# LcsNodes-Diagnostic-Board-B_02_10.net
KiCad netlist of a schematic drawn in EasyEDA
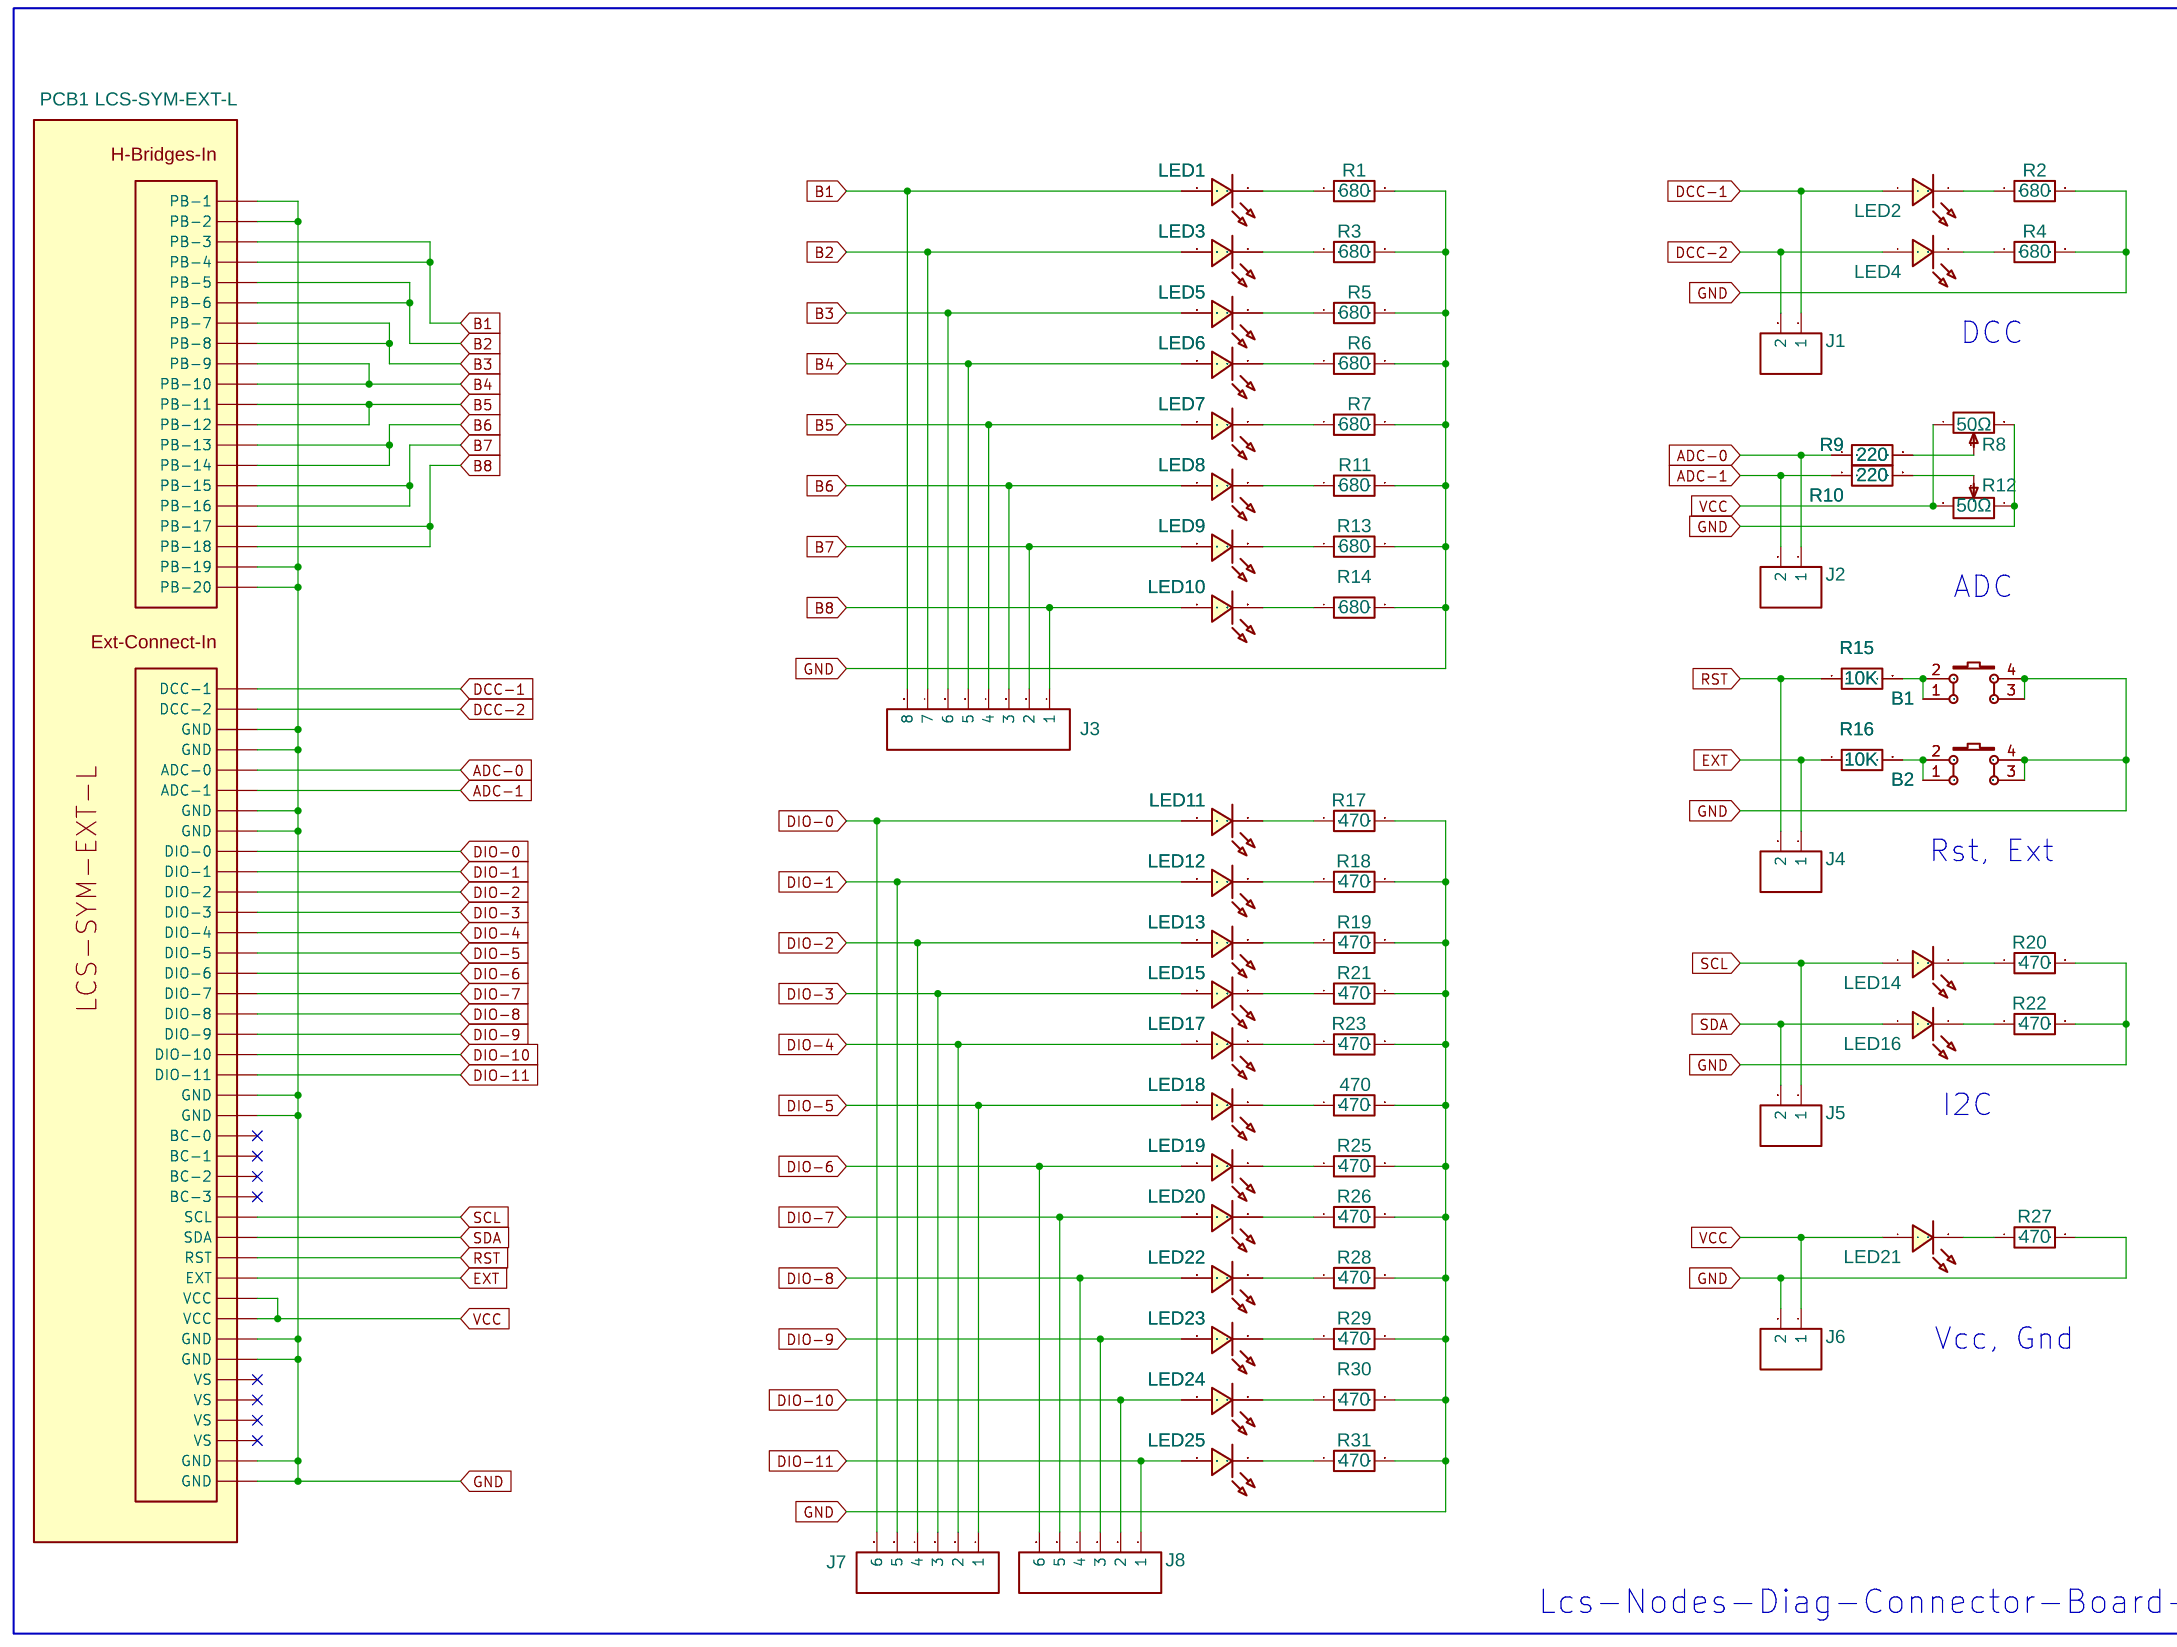
[diagram p0: schematic sheet]

(export (version "E")
  (design (tool "Eeschema 10.0.6"))
  (components
    (comp (ref "470") (value "470") (libsource (lib "") (part "R_0805_EU_1")))
    (comp (ref "B1")
      (value "Opt")
      (fields (field (name "Manufacturer Part") "K2-1102DP-E4SW-04") (field (name "Manufacturer") "韩国韩荣"))
      (libsource (lib "") (part "K4-6×6_TH"))
    )
    (comp (ref "B2")
      (value "Opt")
      (fields (field (name "Manufacturer Part") "K2-1102DP-E4SW-04") (field (name "Manufacturer") "韩国韩荣"))
      (libsource (lib "") (part "K4-6×6_TH"))
    )
    (comp (ref "J1") (value "HDR-M-2.54_1x2") (libsource (lib "") (part "HDR-M-2.54_1x2")))
    (comp (ref "J2") (value "HDR-M-2.54_1x2") (libsource (lib "") (part "HDR-M-2.54_1x2")))
    (comp (ref "J3") (value "HDR-M-2.54_1x8") (libsource (lib "") (part "HDR-M-2.54_1x8")))
    (comp (ref "J4") (value "HDR-M-2.54_1x2") (libsource (lib "") (part "HDR-M-2.54_1x2")))
    (comp (ref "J5") (value "HDR-M-2.54_1x2") (libsource (lib "") (part "HDR-M-2.54_1x2")))
    (comp (ref "J6") (value "HDR-M-2.54_1x2") (libsource (lib "") (part "HDR-M-2.54_1x2")))
    (comp (ref "J7") (value "HDR-M-2.54_1x6") (libsource (lib "") (part "HDR-M-2.54_1x6")))
    (comp (ref "J8") (value "HDR-M-2.54_1x6") (libsource (lib "") (part "HDR-M-2.54_1x6")))
    (comp (ref "LED1")
      (value "LED-0805_G")
      (fields (field (name "Manufacturer Part") "NCD0805G1") (field (name "Manufacturer") "国星光电"))
      (libsource (lib "") (part "LED-0805_G"))
    )
    (comp (ref "LED2")
      (value "LED-0805_G")
      (fields (field (name "Manufacturer Part") "NCD0805G1") (field (name "Manufacturer") "国星光电"))
      (libsource (lib "") (part "LED-0805_G"))
    )
    (comp (ref "LED3")
      (value "LED-0805_G")
      (fields (field (name "Manufacturer Part") "NCD0805G1") (field (name "Manufacturer") "国星光电"))
      (libsource (lib "") (part "LED-0805_G"))
    )
    (comp (ref "LED4")
      (value "LED-0805_G")
      (fields (field (name "Manufacturer Part") "NCD0805G1") (field (name "Manufacturer") "国星光电"))
      (libsource (lib "") (part "LED-0805_G"))
    )
    (comp (ref "LED5")
      (value "LED-0805_G")
      (fields (field (name "Manufacturer Part") "NCD0805G1") (field (name "Manufacturer") "国星光电"))
      (libsource (lib "") (part "LED-0805_G"))
    )
    (comp (ref "LED6")
      (value "LED-0805_G")
      (fields (field (name "Manufacturer Part") "NCD0805G1") (field (name "Manufacturer") "国星光电"))
      (libsource (lib "") (part "LED-0805_G"))
    )
    (comp (ref "LED7")
      (value "LED-0805_G")
      (fields (field (name "Manufacturer Part") "NCD0805G1") (field (name "Manufacturer") "国星光电"))
      (libsource (lib "") (part "LED-0805_G"))
    )
    (comp (ref "LED8")
      (value "LED-0805_G")
      (fields (field (name "Manufacturer Part") "NCD0805G1") (field (name "Manufacturer") "国星光电"))
      (libsource (lib "") (part "LED-0805_G"))
    )
    (comp (ref "LED9")
      (value "LED-0805_G")
      (fields (field (name "Manufacturer Part") "NCD0805G1") (field (name "Manufacturer") "国星光电"))
      (libsource (lib "") (part "LED-0805_G"))
    )
    (comp (ref "LED10")
      (value "LED-0805_G")
      (fields (field (name "Manufacturer Part") "NCD0805G1") (field (name "Manufacturer") "国星光电"))
      (libsource (lib "") (part "LED-0805_G"))
    )
    (comp (ref "LED11")
      (value "LED-0805_G")
      (fields (field (name "Manufacturer Part") "NCD0805G1") (field (name "Manufacturer") "国星光电"))
      (libsource (lib "") (part "LED-0805_G"))
    )
    (comp (ref "LED12")
      (value "LED-0805_G")
      (fields (field (name "Manufacturer Part") "NCD0805G1") (field (name "Manufacturer") "国星光电"))
      (libsource (lib "") (part "LED-0805_G"))
    )
    (comp (ref "LED13")
      (value "LED-0805_G")
      (fields (field (name "Manufacturer Part") "NCD0805G1") (field (name "Manufacturer") "国星光电"))
      (libsource (lib "") (part "LED-0805_G"))
    )
    (comp (ref "LED14")
      (value "LED-0805_G")
      (fields (field (name "Manufacturer Part") "NCD0805G1") (field (name "Manufacturer") "国星光电"))
      (libsource (lib "") (part "LED-0805_G"))
    )
    (comp (ref "LED15")
      (value "LED-0805_G")
      (fields (field (name "Manufacturer Part") "NCD0805G1") (field (name "Manufacturer") "国星光电"))
      (libsource (lib "") (part "LED-0805_G"))
    )
    (comp (ref "LED16")
      (value "LED-0805_G")
      (fields (field (name "Manufacturer Part") "NCD0805G1") (field (name "Manufacturer") "国星光电"))
      (libsource (lib "") (part "LED-0805_G"))
    )
    (comp (ref "LED17")
      (value "LED-0805_G")
      (fields (field (name "Manufacturer Part") "NCD0805G1") (field (name "Manufacturer") "国星光电"))
      (libsource (lib "") (part "LED-0805_G"))
    )
    (comp (ref "LED18")
      (value "LED-0805_G")
      (fields (field (name "Manufacturer Part") "NCD0805G1") (field (name "Manufacturer") "国星光电"))
      (libsource (lib "") (part "LED-0805_G"))
    )
    (comp (ref "LED19")
      (value "LED-0805_G")
      (fields (field (name "Manufacturer Part") "NCD0805G1") (field (name "Manufacturer") "国星光电"))
      (libsource (lib "") (part "LED-0805_G"))
    )
    (comp (ref "LED20")
      (value "LED-0805_G")
      (fields (field (name "Manufacturer Part") "NCD0805G1") (field (name "Manufacturer") "国星光电"))
      (libsource (lib "") (part "LED-0805_G"))
    )
    (comp (ref "LED21")
      (value "LED-0805_G")
      (fields (field (name "Manufacturer Part") "NCD0805G1") (field (name "Manufacturer") "国星光电"))
      (libsource (lib "") (part "LED-0805_G"))
    )
    (comp (ref "LED22")
      (value "LED-0805_G")
      (fields (field (name "Manufacturer Part") "NCD0805G1") (field (name "Manufacturer") "国星光电"))
      (libsource (lib "") (part "LED-0805_G"))
    )
    (comp (ref "LED23")
      (value "LED-0805_G")
      (fields (field (name "Manufacturer Part") "NCD0805G1") (field (name "Manufacturer") "国星光电"))
      (libsource (lib "") (part "LED-0805_G"))
    )
    (comp (ref "LED24")
      (value "LED-0805_G")
      (fields (field (name "Manufacturer Part") "NCD0805G1") (field (name "Manufacturer") "国星光电"))
      (libsource (lib "") (part "LED-0805_G"))
    )
    (comp (ref "LED25")
      (value "LED-0805_G")
      (fields (field (name "Manufacturer Part") "NCD0805G1") (field (name "Manufacturer") "国星光电"))
      (libsource (lib "") (part "LED-0805_G"))
    )
    (comp (ref "PCB1") (value "LCS-SYM-EXT-L") (libsource (lib "") (part "LCS-SYM-EXT-L")))
    (comp (ref "R1") (value "680") (libsource (lib "") (part "R_0805_EU")))
    (comp (ref "R2") (value "680") (libsource (lib "") (part "R_0805_EU")))
    (comp (ref "R3") (value "680") (libsource (lib "") (part "R_0805_EU")))
    (comp (ref "R4") (value "680") (libsource (lib "") (part "R_0805_EU")))
    (comp (ref "R5") (value "680") (libsource (lib "") (part "R_0805_EU")))
    (comp (ref "R6") (value "680") (libsource (lib "") (part "R_0805_EU")))
    (comp (ref "R7") (value "680") (libsource (lib "") (part "R_0805_EU")))
    (comp (ref "R8")
      (value "50Ω")
      (fields
        (field (name "Manufacturer Part") "Precision potentiometer 3296W/50ohm")
        (field (name "Manufacturer") "ReliaPro")
      )
      (libsource (lib "") (part "Precision potentiometer 3296W/50ohm"))
    )
    (comp (ref "R9") (value "220") (libsource (lib "") (part "R_0805_EU")))
    (comp (ref "R10") (value "220") (libsource (lib "") (part "R_0805_EU")))
    (comp (ref "R11") (value "680") (libsource (lib "") (part "R_0805_EU")))
    (comp (ref "R12")
      (value "50Ω")
      (fields
        (field (name "Manufacturer Part") "Precision potentiometer 3296W/50ohm")
        (field (name "Manufacturer") "ReliaPro")
      )
      (libsource (lib "") (part "Precision potentiometer 3296W/50ohm_1"))
    )
    (comp (ref "R13") (value "680") (libsource (lib "") (part "R_0805_EU")))
    (comp (ref "R14") (value "680") (libsource (lib "") (part "R_0805_EU")))
    (comp (ref "R15") (value "10K") (libsource (lib "") (part "R_0805_EU")))
    (comp (ref "R16") (value "10K") (libsource (lib "") (part "R_0805_EU")))
    (comp (ref "R17") (value "470") (libsource (lib "") (part "R_0805_EU")))
    (comp (ref "R18") (value "470") (libsource (lib "") (part "R_0805_EU")))
    (comp (ref "R19") (value "470") (libsource (lib "") (part "R_0805_EU")))
    (comp (ref "R20") (value "470") (libsource (lib "") (part "R_0805_EU")))
    (comp (ref "R21") (value "470") (libsource (lib "") (part "R_0805_EU")))
    (comp (ref "R22") (value "470") (libsource (lib "") (part "R_0805_EU")))
    (comp (ref "R23") (value "470") (libsource (lib "") (part "R_0805_EU")))
    (comp (ref "R25") (value "470") (libsource (lib "") (part "R_0805_EU")))
    (comp (ref "R26") (value "470") (libsource (lib "") (part "R_0805_EU")))
    (comp (ref "R27") (value "470") (libsource (lib "") (part "R_0805_EU")))
    (comp (ref "R28") (value "470") (libsource (lib "") (part "R_0805_EU")))
    (comp (ref "R29") (value "470") (libsource (lib "") (part "R_0805_EU")))
    (comp (ref "R30") (value "470") (libsource (lib "") (part "R_0805_EU")))
    (comp (ref "R31") (value "470") (libsource (lib "") (part "R_0805_EU")))
  )
  (nets
    (net (code "1") (name "ADC-0") (class "Default")
      (node (ref "J2") (pin "1") (pinfunction "1_1") (pintype "unspecified"))
      (node (ref "PCB1") (pin "64") (pinfunction "ADC-0_64") (pintype "unspecified"))
      (node (ref "R9") (pin "1") (pinfunction "1_1") (pintype "unspecified"))
    )
    (net (code "2") (name "ADC-1") (class "Default")
      (node (ref "J2") (pin "2") (pinfunction "2_2") (pintype "unspecified"))
      (node (ref "PCB1") (pin "65") (pinfunction "ADC-1_65") (pintype "unspecified"))
      (node (ref "R10") (pin "1") (pinfunction "1_1") (pintype "unspecified"))
    )
    (net (code "3") (name "B1") (class "Default")
      (node (ref "J3") (pin "8") (pinfunction "8_8") (pintype "unspecified"))
      (node (ref "LED1") (pin "1") (pinfunction "1_1") (pintype "unspecified"))
      (node (ref "PCB1") (pin "32") (pinfunction "PB-3_32") (pintype "unspecified"))
      (node (ref "PCB1") (pin "33") (pinfunction "PB-4_33") (pintype "unspecified"))
    )
    (net (code "4") (name "B2") (class "Default")
      (node (ref "J3") (pin "7") (pinfunction "7_7") (pintype "unspecified"))
      (node (ref "LED3") (pin "1") (pinfunction "1_1") (pintype "unspecified"))
      (node (ref "PCB1") (pin "34") (pinfunction "PB-5_34") (pintype "unspecified"))
      (node (ref "PCB1") (pin "35") (pinfunction "PB-6_35") (pintype "unspecified"))
    )
    (net (code "5") (name "B3") (class "Default")
      (node (ref "J3") (pin "6") (pinfunction "6_6") (pintype "unspecified"))
      (node (ref "LED5") (pin "1") (pinfunction "1_1") (pintype "unspecified"))
      (node (ref "PCB1") (pin "36") (pinfunction "PB-7_36") (pintype "unspecified"))
      (node (ref "PCB1") (pin "37") (pinfunction "PB-8_37") (pintype "unspecified"))
    )
    (net (code "6") (name "B4") (class "Default")
      (node (ref "J3") (pin "5") (pinfunction "5_5") (pintype "unspecified"))
      (node (ref "LED6") (pin "1") (pinfunction "1_1") (pintype "unspecified"))
      (node (ref "PCB1") (pin "38") (pinfunction "PB-9_38") (pintype "unspecified"))
      (node (ref "PCB1") (pin "39") (pinfunction "PB-10_39") (pintype "unspecified"))
    )
    (net (code "7") (name "B5") (class "Default")
      (node (ref "J3") (pin "4") (pinfunction "4_4") (pintype "unspecified"))
      (node (ref "LED7") (pin "1") (pinfunction "1_1") (pintype "unspecified"))
      (node (ref "PCB1") (pin "40") (pinfunction "PB-11_40") (pintype "unspecified"))
      (node (ref "PCB1") (pin "41") (pinfunction "PB-12_41") (pintype "unspecified"))
    )
    (net (code "8") (name "B6") (class "Default")
      (node (ref "J3") (pin "3") (pinfunction "3_3") (pintype "unspecified"))
      (node (ref "LED8") (pin "1") (pinfunction "1_1") (pintype "unspecified"))
      (node (ref "PCB1") (pin "42") (pinfunction "PB-13_42") (pintype "unspecified"))
      (node (ref "PCB1") (pin "43") (pinfunction "PB-14_43") (pintype "unspecified"))
    )
    (net (code "9") (name "B7") (class "Default")
      (node (ref "J3") (pin "2") (pinfunction "2_2") (pintype "unspecified"))
      (node (ref "LED9") (pin "1") (pinfunction "1_1") (pintype "unspecified"))
      (node (ref "PCB1") (pin "44") (pinfunction "PB-15_44") (pintype "unspecified"))
      (node (ref "PCB1") (pin "45") (pinfunction "PB-16_45") (pintype "unspecified"))
    )
    (net (code "10") (name "B8") (class "Default")
      (node (ref "J3") (pin "1") (pinfunction "1_1") (pintype "unspecified"))
      (node (ref "LED10") (pin "1") (pinfunction "1_1") (pintype "unspecified"))
      (node (ref "PCB1") (pin "46") (pinfunction "PB-17_46") (pintype "unspecified"))
      (node (ref "PCB1") (pin "47") (pinfunction "PB-18_47") (pintype "unspecified"))
    )
    (net (code "11") (name "DCC-1") (class "Default")
      (node (ref "J1") (pin "1") (pinfunction "1_1") (pintype "unspecified"))
      (node (ref "LED2") (pin "1") (pinfunction "1_1") (pintype "unspecified"))
      (node (ref "PCB1") (pin "60") (pinfunction "DCC-1_60") (pintype "unspecified"))
    )
    (net (code "12") (name "DCC-2") (class "Default")
      (node (ref "J1") (pin "2") (pinfunction "2_2") (pintype "unspecified"))
      (node (ref "LED4") (pin "1") (pinfunction "1_1") (pintype "unspecified"))
      (node (ref "PCB1") (pin "61") (pinfunction "DCC-2_61") (pintype "unspecified"))
    )
    (net (code "13") (name "DIO-0") (class "Default")
      (node (ref "J7") (pin "6") (pinfunction "6_6") (pintype "input"))
      (node (ref "LED11") (pin "1") (pinfunction "1_1") (pintype "unspecified"))
      (node (ref "PCB1") (pin "68") (pinfunction "DIO-0_68") (pintype "unspecified"))
    )
    (net (code "14") (name "DIO-1") (class "Default")
      (node (ref "J7") (pin "5") (pinfunction "5_5") (pintype "input"))
      (node (ref "LED12") (pin "1") (pinfunction "1_1") (pintype "unspecified"))
      (node (ref "PCB1") (pin "69") (pinfunction "DIO-1_69") (pintype "unspecified"))
    )
    (net (code "15") (name "DIO-2") (class "Default")
      (node (ref "J7") (pin "4") (pinfunction "4_4") (pintype "input"))
      (node (ref "LED13") (pin "1") (pinfunction "1_1") (pintype "unspecified"))
      (node (ref "PCB1") (pin "70") (pinfunction "DIO-2_70") (pintype "unspecified"))
    )
    (net (code "16") (name "DIO-3") (class "Default")
      (node (ref "J7") (pin "3") (pinfunction "3_3") (pintype "input"))
      (node (ref "LED15") (pin "1") (pinfunction "1_1") (pintype "unspecified"))
      (node (ref "PCB1") (pin "71") (pinfunction "DIO-3_71") (pintype "unspecified"))
    )
    (net (code "17") (name "DIO-4") (class "Default")
      (node (ref "J7") (pin "2") (pinfunction "2_2") (pintype "input"))
      (node (ref "LED17") (pin "1") (pinfunction "1_1") (pintype "unspecified"))
      (node (ref "PCB1") (pin "72") (pinfunction "DIO-4_72") (pintype "unspecified"))
    )
    (net (code "18") (name "DIO-5") (class "Default")
      (node (ref "J7") (pin "1") (pinfunction "1_1") (pintype "input"))
      (node (ref "LED18") (pin "1") (pinfunction "1_1") (pintype "unspecified"))
      (node (ref "PCB1") (pin "73") (pinfunction "DIO-5_73") (pintype "unspecified"))
    )
    (net (code "19") (name "DIO-6") (class "Default")
      (node (ref "J8") (pin "6") (pinfunction "6_6") (pintype "input"))
      (node (ref "LED19") (pin "1") (pinfunction "1_1") (pintype "unspecified"))
      (node (ref "PCB1") (pin "74") (pinfunction "DIO-6_74") (pintype "unspecified"))
    )
    (net (code "20") (name "DIO-7") (class "Default")
      (node (ref "J8") (pin "5") (pinfunction "5_5") (pintype "input"))
      (node (ref "LED20") (pin "1") (pinfunction "1_1") (pintype "unspecified"))
      (node (ref "PCB1") (pin "75") (pinfunction "DIO-7_75") (pintype "unspecified"))
    )
    (net (code "21") (name "DIO-8") (class "Default")
      (node (ref "J8") (pin "4") (pinfunction "4_4") (pintype "input"))
      (node (ref "LED22") (pin "1") (pinfunction "1_1") (pintype "unspecified"))
      (node (ref "PCB1") (pin "76") (pinfunction "DIO-8_76") (pintype "unspecified"))
    )
    (net (code "22") (name "DIO-9") (class "Default")
      (node (ref "J8") (pin "3") (pinfunction "3_3") (pintype "input"))
      (node (ref "LED23") (pin "1") (pinfunction "1_1") (pintype "unspecified"))
      (node (ref "PCB1") (pin "77") (pinfunction "DIO-9_77") (pintype "unspecified"))
    )
    (net (code "23") (name "DIO-10") (class "Default")
      (node (ref "J8") (pin "2") (pinfunction "2_2") (pintype "input"))
      (node (ref "LED24") (pin "1") (pinfunction "1_1") (pintype "unspecified"))
      (node (ref "PCB1") (pin "78") (pinfunction "DIO-10_78") (pintype "unspecified"))
    )
    (net (code "24") (name "DIO-11") (class "Default")
      (node (ref "J8") (pin "1") (pinfunction "1_1") (pintype "input"))
      (node (ref "LED25") (pin "1") (pinfunction "1_1") (pintype "unspecified"))
      (node (ref "PCB1") (pin "79") (pinfunction "DIO-11_79") (pintype "unspecified"))
    )
    (net (code "25") (name "EXT") (class "Default")
      (node (ref "J4") (pin "1") (pinfunction "1_1") (pintype "unspecified"))
      (node (ref "PCB1") (pin "89") (pinfunction "EXT_89") (pintype "unspecified"))
      (node (ref "R16") (pin "1") (pinfunction "1_1") (pintype "unspecified"))
    )
    (net (code "26") (name "GND") (class "Default")
      (node (ref "470") (pin "2") (pinfunction "2_2") (pintype "unspecified"))
      (node (ref "B1") (pin "3") (pinfunction "3_3") (pintype "unspecified"))
      (node (ref "B1") (pin "4") (pinfunction "4_4") (pintype "unspecified"))
      (node (ref "B2") (pin "3") (pinfunction "3_3") (pintype "unspecified"))
      (node (ref "B2") (pin "4") (pinfunction "4_4") (pintype "unspecified"))
      (node (ref "J6") (pin "2") (pinfunction "2_2") (pintype "unspecified"))
      (node (ref "PCB1") (pin "30") (pinfunction "PB-1_30") (pintype "unspecified"))
      (node (ref "PCB1") (pin "31") (pinfunction "PB-2_31") (pintype "unspecified"))
      (node (ref "PCB1") (pin "48") (pinfunction "PB-19_48") (pintype "unspecified"))
      (node (ref "PCB1") (pin "49") (pinfunction "PB-20_49") (pintype "unspecified"))
      (node (ref "PCB1") (pin "62") (pinfunction "GND_62") (pintype "unspecified"))
      (node (ref "PCB1") (pin "63") (pinfunction "GND_63") (pintype "unspecified"))
      (node (ref "PCB1") (pin "66") (pinfunction "GND_66") (pintype "unspecified"))
      (node (ref "PCB1") (pin "67") (pinfunction "GND_67") (pintype "unspecified"))
      (node (ref "PCB1") (pin "80") (pinfunction "GND_80") (pintype "unspecified"))
      (node (ref "PCB1") (pin "81") (pinfunction "GND_81") (pintype "unspecified"))
      (node (ref "PCB1") (pin "92") (pinfunction "GND_92") (pintype "unspecified"))
      (node (ref "PCB1") (pin "93") (pinfunction "GND_93") (pintype "unspecified"))
      (node (ref "PCB1") (pin "98") (pinfunction "GND_98") (pintype "unspecified"))
      (node (ref "PCB1") (pin "99") (pinfunction "GND_99") (pintype "unspecified"))
      (node (ref "R1") (pin "2") (pinfunction "2_2") (pintype "unspecified"))
      (node (ref "R11") (pin "2") (pinfunction "2_2") (pintype "unspecified"))
      (node (ref "R12") (pin "1") (pinfunction "1_1") (pintype "input"))
      (node (ref "R13") (pin "2") (pinfunction "2_2") (pintype "unspecified"))
      (node (ref "R14") (pin "2") (pinfunction "2_2") (pintype "unspecified"))
      (node (ref "R17") (pin "2") (pinfunction "2_2") (pintype "unspecified"))
      (node (ref "R18") (pin "2") (pinfunction "2_2") (pintype "unspecified"))
      (node (ref "R19") (pin "2") (pinfunction "2_2") (pintype "unspecified"))
      (node (ref "R2") (pin "2") (pinfunction "2_2") (pintype "unspecified"))
      (node (ref "R20") (pin "2") (pinfunction "2_2") (pintype "unspecified"))
      (node (ref "R21") (pin "2") (pinfunction "2_2") (pintype "unspecified"))
      (node (ref "R22") (pin "2") (pinfunction "2_2") (pintype "unspecified"))
      (node (ref "R23") (pin "2") (pinfunction "2_2") (pintype "unspecified"))
      (node (ref "R25") (pin "2") (pinfunction "2_2") (pintype "unspecified"))
      (node (ref "R26") (pin "2") (pinfunction "2_2") (pintype "unspecified"))
      (node (ref "R27") (pin "2") (pinfunction "2_2") (pintype "unspecified"))
      (node (ref "R28") (pin "2") (pinfunction "2_2") (pintype "unspecified"))
      (node (ref "R29") (pin "2") (pinfunction "2_2") (pintype "unspecified"))
      (node (ref "R3") (pin "2") (pinfunction "2_2") (pintype "unspecified"))
      (node (ref "R30") (pin "2") (pinfunction "2_2") (pintype "unspecified"))
      (node (ref "R31") (pin "2") (pinfunction "2_2") (pintype "unspecified"))
      (node (ref "R4") (pin "2") (pinfunction "2_2") (pintype "unspecified"))
      (node (ref "R5") (pin "2") (pinfunction "2_2") (pintype "unspecified"))
      (node (ref "R6") (pin "2") (pinfunction "2_2") (pintype "unspecified"))
      (node (ref "R7") (pin "2") (pinfunction "2_2") (pintype "unspecified"))
      (node (ref "R8") (pin "3") (pinfunction "3_3") (pintype "input"))
    )
    (net (code "27") (name "Net-(470-Pad1)") (class "Default")
      (node (ref "470") (pin "1") (pinfunction "1_1") (pintype "unspecified"))
      (node (ref "LED18") (pin "2") (pinfunction "2_2") (pintype "unspecified"))
    )
    (net (code "28") (name "Net-(B1-Pad1)") (class "Default")
      (node (ref "B1") (pin "1") (pinfunction "1_1") (pintype "unspecified"))
      (node (ref "B1") (pin "2") (pinfunction "2_2") (pintype "unspecified"))
      (node (ref "R15") (pin "2") (pinfunction "2_2") (pintype "unspecified"))
    )
    (net (code "29") (name "Net-(B2-Pad1)") (class "Default")
      (node (ref "B2") (pin "1") (pinfunction "1_1") (pintype "unspecified"))
      (node (ref "B2") (pin "2") (pinfunction "2_2") (pintype "unspecified"))
      (node (ref "R16") (pin "2") (pinfunction "2_2") (pintype "unspecified"))
    )
    (net (code "30") (name "Net-(LED1-Pad2)") (class "Default")
      (node (ref "LED1") (pin "2") (pinfunction "2_2") (pintype "unspecified"))
      (node (ref "R1") (pin "1") (pinfunction "1_1") (pintype "unspecified"))
    )
    (net (code "31") (name "Net-(LED2-Pad2)") (class "Default")
      (node (ref "LED2") (pin "2") (pinfunction "2_2") (pintype "unspecified"))
      (node (ref "R2") (pin "1") (pinfunction "1_1") (pintype "unspecified"))
    )
    (net (code "32") (name "Net-(LED3-Pad2)") (class "Default")
      (node (ref "LED3") (pin "2") (pinfunction "2_2") (pintype "unspecified"))
      (node (ref "R3") (pin "1") (pinfunction "1_1") (pintype "unspecified"))
    )
    (net (code "33") (name "Net-(LED4-Pad2)") (class "Default")
      (node (ref "LED4") (pin "2") (pinfunction "2_2") (pintype "unspecified"))
      (node (ref "R4") (pin "1") (pinfunction "1_1") (pintype "unspecified"))
    )
    (net (code "34") (name "Net-(LED5-Pad2)") (class "Default")
      (node (ref "LED5") (pin "2") (pinfunction "2_2") (pintype "unspecified"))
      (node (ref "R5") (pin "1") (pinfunction "1_1") (pintype "unspecified"))
    )
    (net (code "35") (name "Net-(LED6-Pad2)") (class "Default")
      (node (ref "LED6") (pin "2") (pinfunction "2_2") (pintype "unspecified"))
      (node (ref "R6") (pin "1") (pinfunction "1_1") (pintype "unspecified"))
    )
    (net (code "36") (name "Net-(LED7-Pad2)") (class "Default")
      (node (ref "LED7") (pin "2") (pinfunction "2_2") (pintype "unspecified"))
      (node (ref "R7") (pin "1") (pinfunction "1_1") (pintype "unspecified"))
    )
    (net (code "37") (name "Net-(LED8-Pad2)") (class "Default")
      (node (ref "LED8") (pin "2") (pinfunction "2_2") (pintype "unspecified"))
      (node (ref "R11") (pin "1") (pinfunction "1_1") (pintype "unspecified"))
    )
    (net (code "38") (name "Net-(LED9-Pad2)") (class "Default")
      (node (ref "LED9") (pin "2") (pinfunction "2_2") (pintype "unspecified"))
      (node (ref "R13") (pin "1") (pinfunction "1_1") (pintype "unspecified"))
    )
    (net (code "39") (name "Net-(LED10-Pad2)") (class "Default")
      (node (ref "LED10") (pin "2") (pinfunction "2_2") (pintype "unspecified"))
      (node (ref "R14") (pin "1") (pinfunction "1_1") (pintype "unspecified"))
    )
    (net (code "40") (name "Net-(LED11-Pad2)") (class "Default")
      (node (ref "LED11") (pin "2") (pinfunction "2_2") (pintype "unspecified"))
      (node (ref "R17") (pin "1") (pinfunction "1_1") (pintype "unspecified"))
    )
    (net (code "41") (name "Net-(LED12-Pad2)") (class "Default")
      (node (ref "LED12") (pin "2") (pinfunction "2_2") (pintype "unspecified"))
      (node (ref "R18") (pin "1") (pinfunction "1_1") (pintype "unspecified"))
    )
    (net (code "42") (name "Net-(LED13-Pad2)") (class "Default")
      (node (ref "LED13") (pin "2") (pinfunction "2_2") (pintype "unspecified"))
      (node (ref "R19") (pin "1") (pinfunction "1_1") (pintype "unspecified"))
    )
    (net (code "43") (name "Net-(LED14-Pad2)") (class "Default")
      (node (ref "LED14") (pin "2") (pinfunction "2_2") (pintype "unspecified"))
      (node (ref "R20") (pin "1") (pinfunction "1_1") (pintype "unspecified"))
    )
    (net (code "44") (name "Net-(LED15-Pad2)") (class "Default")
      (node (ref "LED15") (pin "2") (pinfunction "2_2") (pintype "unspecified"))
      (node (ref "R21") (pin "1") (pinfunction "1_1") (pintype "unspecified"))
    )
    (net (code "45") (name "Net-(LED16-Pad2)") (class "Default")
      (node (ref "LED16") (pin "2") (pinfunction "2_2") (pintype "unspecified"))
      (node (ref "R22") (pin "1") (pinfunction "1_1") (pintype "unspecified"))
    )
    (net (code "46") (name "Net-(LED17-Pad2)") (class "Default")
      (node (ref "LED17") (pin "2") (pinfunction "2_2") (pintype "unspecified"))
      (node (ref "R23") (pin "1") (pinfunction "1_1") (pintype "unspecified"))
    )
    (net (code "47") (name "Net-(LED19-Pad2)") (class "Default")
      (node (ref "LED19") (pin "2") (pinfunction "2_2") (pintype "unspecified"))
      (node (ref "R25") (pin "1") (pinfunction "1_1") (pintype "unspecified"))
    )
    (net (code "48") (name "Net-(LED20-Pad2)") (class "Default")
      (node (ref "LED20") (pin "2") (pinfunction "2_2") (pintype "unspecified"))
      (node (ref "R26") (pin "1") (pinfunction "1_1") (pintype "unspecified"))
    )
    (net (code "49") (name "Net-(LED21-Pad2)") (class "Default")
      (node (ref "LED21") (pin "2") (pinfunction "2_2") (pintype "unspecified"))
      (node (ref "R27") (pin "1") (pinfunction "1_1") (pintype "unspecified"))
    )
    (net (code "50") (name "Net-(LED22-Pad2)") (class "Default")
      (node (ref "LED22") (pin "2") (pinfunction "2_2") (pintype "unspecified"))
      (node (ref "R28") (pin "1") (pinfunction "1_1") (pintype "unspecified"))
    )
    (net (code "51") (name "Net-(LED23-Pad2)") (class "Default")
      (node (ref "LED23") (pin "2") (pinfunction "2_2") (pintype "unspecified"))
      (node (ref "R29") (pin "1") (pinfunction "1_1") (pintype "unspecified"))
    )
    (net (code "52") (name "Net-(LED24-Pad2)") (class "Default")
      (node (ref "LED24") (pin "2") (pinfunction "2_2") (pintype "unspecified"))
      (node (ref "R30") (pin "1") (pinfunction "1_1") (pintype "unspecified"))
    )
    (net (code "53") (name "Net-(LED25-Pad2)") (class "Default")
      (node (ref "LED25") (pin "2") (pinfunction "2_2") (pintype "unspecified"))
      (node (ref "R31") (pin "1") (pinfunction "1_1") (pintype "unspecified"))
    )
    (net (code "54") (name "Net-(R8-Pad2)") (class "Default")
      (node (ref "R8") (pin "2") (pinfunction "2_2") (pintype "input"))
      (node (ref "R9") (pin "2") (pinfunction "2_2") (pintype "unspecified"))
    )
    (net (code "55") (name "Net-(R10-Pad2)") (class "Default")
      (node (ref "R10") (pin "2") (pinfunction "2_2") (pintype "unspecified"))
      (node (ref "R12") (pin "2") (pinfunction "2_2") (pintype "input"))
    )
    (net (code "56") (name "RST") (class "Default")
      (node (ref "J4") (pin "2") (pinfunction "2_2") (pintype "unspecified"))
      (node (ref "PCB1") (pin "88") (pinfunction "RST_88") (pintype "unspecified"))
      (node (ref "R15") (pin "1") (pinfunction "1_1") (pintype "unspecified"))
    )
    (net (code "57") (name "SCL") (class "Default")
      (node (ref "J5") (pin "1") (pinfunction "1_1") (pintype "unspecified"))
      (node (ref "LED14") (pin "1") (pinfunction "1_1") (pintype "unspecified"))
      (node (ref "PCB1") (pin "86") (pinfunction "SCL_86") (pintype "unspecified"))
    )
    (net (code "58") (name "SDA") (class "Default")
      (node (ref "J5") (pin "2") (pinfunction "2_2") (pintype "unspecified"))
      (node (ref "LED16") (pin "1") (pinfunction "1_1") (pintype "unspecified"))
      (node (ref "PCB1") (pin "87") (pinfunction "SDA_87") (pintype "unspecified"))
    )
    (net (code "59") (name "VCC") (class "Default")
      (node (ref "J6") (pin "1") (pinfunction "1_1") (pintype "unspecified"))
      (node (ref "LED21") (pin "1") (pinfunction "1_1") (pintype "unspecified"))
      (node (ref "PCB1") (pin "90") (pinfunction "VCC_90") (pintype "unspecified"))
      (node (ref "PCB1") (pin "91") (pinfunction "VCC_91") (pintype "unspecified"))
      (node (ref "R12") (pin "3") (pinfunction "3_3") (pintype "input"))
      (node (ref "R8") (pin "1") (pinfunction "1_1") (pintype "input"))
    )
    (net (code "60") (name "unconnected-(PCB1-BC-0-Pad82)") (class "Default")
      (node (ref "PCB1") (pin "82") (pinfunction "BC-0_82") (pintype "unspecified+no_connect"))
    )
    (net (code "61") (name "unconnected-(PCB1-BC-1-Pad83)") (class "Default")
      (node (ref "PCB1") (pin "83") (pinfunction "BC-1_83") (pintype "unspecified+no_connect"))
    )
    (net (code "62") (name "unconnected-(PCB1-BC-2-Pad84)") (class "Default")
      (node (ref "PCB1") (pin "84") (pinfunction "BC-2_84") (pintype "unspecified+no_connect"))
    )
    (net (code "63") (name "unconnected-(PCB1-BC-3-Pad85)") (class "Default")
      (node (ref "PCB1") (pin "85") (pinfunction "BC-3_85") (pintype "unspecified+no_connect"))
    )
    (net (code "64") (name "unconnected-(PCB1-VS-Pad94)") (class "Default")
      (node (ref "PCB1") (pin "94") (pinfunction "VS_94") (pintype "unspecified+no_connect"))
    )
    (net (code "65") (name "unconnected-(PCB1-VS-Pad95)") (class "Default")
      (node (ref "PCB1") (pin "95") (pinfunction "VS_95") (pintype "unspecified+no_connect"))
    )
    (net (code "66") (name "unconnected-(PCB1-VS-Pad96)") (class "Default")
      (node (ref "PCB1") (pin "96") (pinfunction "VS_96") (pintype "unspecified+no_connect"))
    )
    (net (code "67") (name "unconnected-(PCB1-VS-Pad97)") (class "Default")
      (node (ref "PCB1") (pin "97") (pinfunction "VS_97") (pintype "unspecified+no_connect"))
    )
  )
)
